# supply_test_2v0.net
KiCad netlist of a schematic drawn in EAGLE
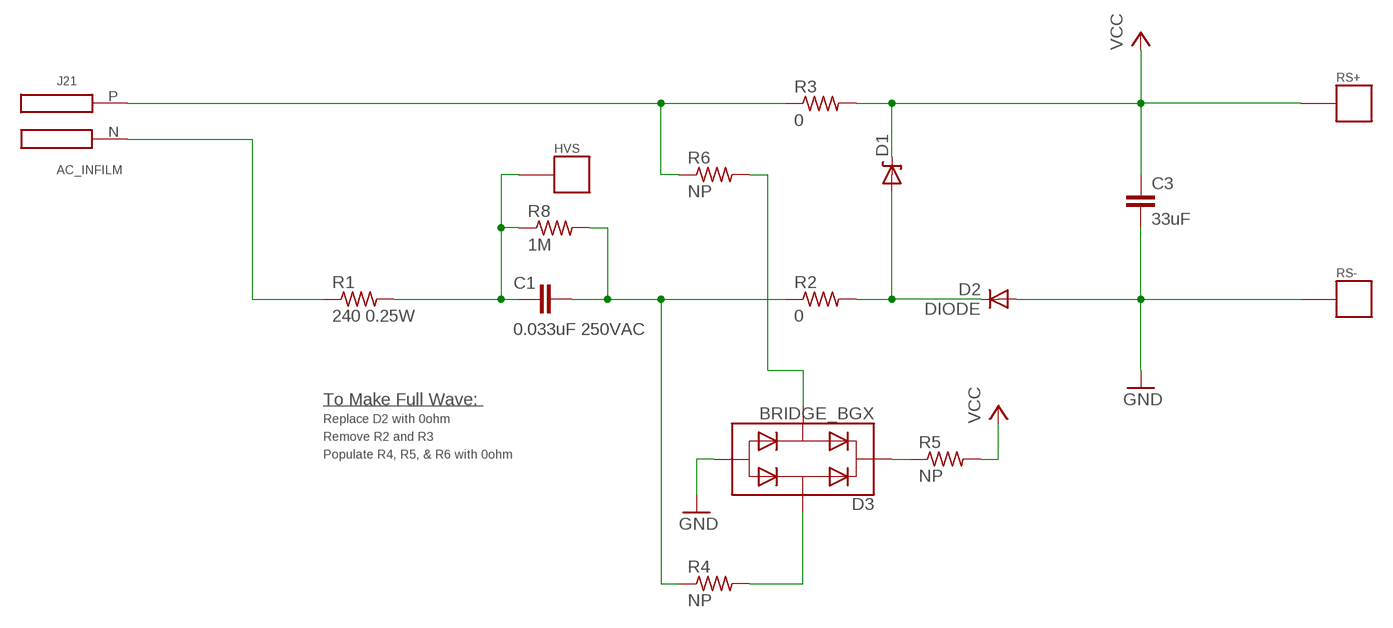
[diagram p0: schematic, sheet 1]
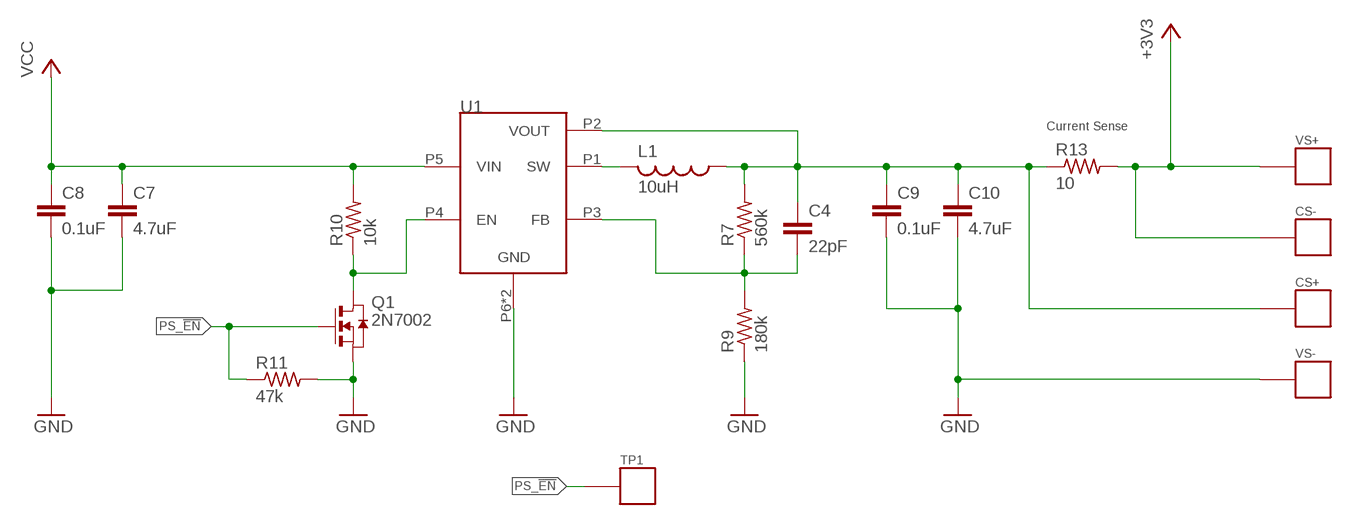
[diagram p1: schematic, sheet 2]
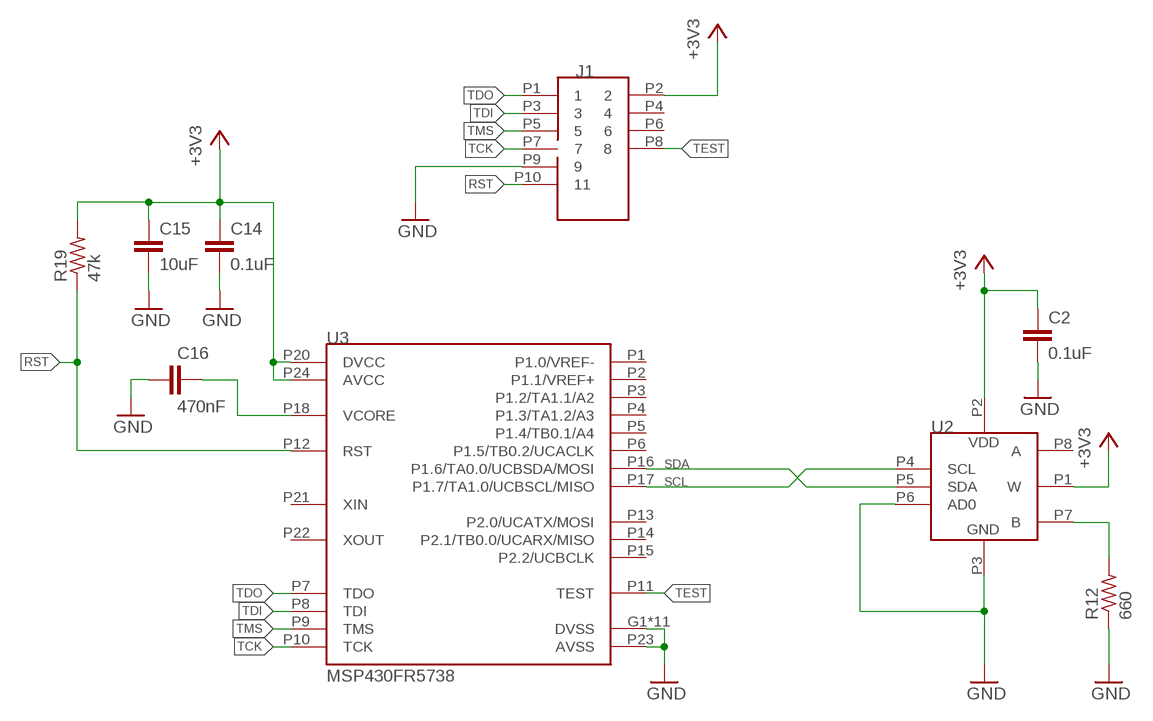
[diagram p2: schematic, sheet 3]

(export (version "E")
  (design (tool "Eeschema 10.0.6"))
  (components
    (comp (ref "C1")
      (value "0.033uF 250VAC")
      (footprint "eagle-import:C2220K")
      (libsource (lib "eagle-import") (part "C-EUC2220K"))
    )
    (comp (ref "C3")
      (value "33uF")
      (footprint "eagle-import:C0603")
      (libsource (lib "eagle-import") (part "C-EUC0603"))
    )
    (comp (ref "D1")
      (value "ZENERBZT52")
      (footprint "eagle-import:BZT52")
      (fields (field (name "DIGIKEY") "BZT52C10T-7DICT-ND "))
      (libsource (lib "eagle-import") (part "ZENERBZT52"))
    )
    (comp (ref "D2")
      (value "DIODE")
      (footprint "eagle-import:BAS521")
      (libsource (lib "eagle-import") (part "DIODE"))
    )
    (comp (ref "D3")
      (value "BRIDGE_BGX")
      (footprint "eagle-import:TO-253-4")
      (libsource (lib "eagle-import") (part "BRIDGE_BGX"))
    )
    (comp (ref "HVS")
      (value "TP_STD")
      (footprint "eagle-import:TP")
      (libsource (lib "eagle-import") (part "TP_STD"))
    )
    (comp (ref "J21")
      (value "AC_INFILM")
      (footprint "eagle-import:AC3_FILM")
      (libsource (lib "eagle-import") (part "AC_INFILM"))
    )
    (comp (ref "R1")
      (value "240 0.25W")
      (footprint "eagle-import:R0603")
      (libsource (lib "eagle-import") (part "R-US_R0603"))
    )
    (comp (ref "R2")
      (value "0")
      (footprint "eagle-import:R0603")
      (libsource (lib "eagle-import") (part "R-US_R0603"))
    )
    (comp (ref "R3")
      (value "0")
      (footprint "eagle-import:R0603")
      (libsource (lib "eagle-import") (part "R-US_R0603"))
    )
    (comp (ref "R4")
      (value "NP")
      (footprint "eagle-import:R0603")
      (libsource (lib "eagle-import") (part "R-US_R0603"))
    )
    (comp (ref "R5")
      (value "NP")
      (footprint "eagle-import:R0603")
      (libsource (lib "eagle-import") (part "R-US_R0603"))
    )
    (comp (ref "R6")
      (value "NP")
      (footprint "eagle-import:R0603")
      (libsource (lib "eagle-import") (part "R-US_R0603"))
    )
    (comp (ref "R8")
      (value "1M")
      (footprint "eagle-import:R0603")
      (libsource (lib "eagle-import") (part "R-US_R0603"))
    )
    (comp (ref "RS+")
      (value "TP_STD")
      (footprint "eagle-import:TP")
      (libsource (lib "eagle-import") (part "TP_STD"))
    )
    (comp (ref "RS-")
      (value "TP_STD")
      (footprint "eagle-import:TP")
      (libsource (lib "eagle-import") (part "TP_STD"))
    )
    (comp (ref "C4")
      (value "22pF")
      (footprint "eagle-import:C0603")
      (libsource (lib "eagle-import") (part "C-EUC0603"))
    )
    (comp (ref "C7")
      (value "4.7uF")
      (footprint "eagle-import:C0402")
      (libsource (lib "eagle-import") (part "C-EUC0402"))
    )
    (comp (ref "C8")
      (value "0.1uF")
      (footprint "eagle-import:C0402")
      (libsource (lib "eagle-import") (part "C-EUC0402"))
    )
    (comp (ref "C9")
      (value "0.1uF")
      (footprint "eagle-import:C0402")
      (libsource (lib "eagle-import") (part "C-EUC0402"))
    )
    (comp (ref "C10")
      (value "4.7uF")
      (footprint "eagle-import:C0603")
      (libsource (lib "eagle-import") (part "C-EUC0603"))
    )
    (comp (ref "CS+")
      (value "TP_STD")
      (footprint "eagle-import:TP")
      (libsource (lib "eagle-import") (part "TP_STD"))
    )
    (comp (ref "CS-")
      (value "TP_STD")
      (footprint "eagle-import:TP")
      (libsource (lib "eagle-import") (part "TP_STD"))
    )
    (comp (ref "L1")
      (value "10uH")
      (footprint "eagle-import:L0805")
      (libsource (lib "eagle-import") (part "L-USL0805"))
    )
    (comp (ref "Q1")
      (value "2N7002")
      (footprint "eagle-import:SC-70-3")
      (libsource (lib "eagle-import") (part "2N7002"))
    )
    (comp (ref "R7")
      (value "560k")
      (footprint "eagle-import:R0603")
      (libsource (lib "eagle-import") (part "R-US_R0603"))
    )
    (comp (ref "R9")
      (value "180k")
      (footprint "eagle-import:R0603")
      (libsource (lib "eagle-import") (part "R-US_R0603"))
    )
    (comp (ref "R10")
      (value "10k")
      (footprint "eagle-import:R0402")
      (libsource (lib "eagle-import") (part "R-US_R0402"))
    )
    (comp (ref "R11")
      (value "47k")
      (footprint "eagle-import:R0603")
      (libsource (lib "eagle-import") (part "R-US_R0603"))
    )
    (comp (ref "R13")
      (value "10")
      (footprint "eagle-import:R0603")
      (libsource (lib "eagle-import") (part "R-US_R0603"))
    )
    (comp (ref "TP1")
      (value "TP_STD")
      (footprint "eagle-import:TP")
      (libsource (lib "eagle-import") (part "TP_STD"))
    )
    (comp (ref "U1")
      (value "TPS62122")
      (footprint "eagle-import:WDFN-6")
      (libsource (lib "eagle-import") (part "TPS62122"))
    )
    (comp (ref "VS+")
      (value "TP_STD")
      (footprint "eagle-import:TP")
      (libsource (lib "eagle-import") (part "TP_STD"))
    )
    (comp (ref "VS-")
      (value "TP_STD")
      (footprint "eagle-import:TP")
      (libsource (lib "eagle-import") (part "TP_STD"))
    )
    (comp (ref "C2")
      (value "0.1uF")
      (footprint "eagle-import:C0603")
      (libsource (lib "eagle-import") (part "C-EUC0603"))
    )
    (comp (ref "C14")
      (value "0.1uF")
      (footprint "eagle-import:C0603")
      (libsource (lib "eagle-import") (part "C-EUC0603"))
    )
    (comp (ref "C15")
      (value "10uF")
      (footprint "eagle-import:C0603")
      (libsource (lib "eagle-import") (part "C-EUC0603"))
    )
    (comp (ref "C16")
      (value "470nF")
      (footprint "eagle-import:C0603")
      (libsource (lib "eagle-import") (part "C-EUC0603"))
    )
    (comp (ref "J1")
      (value "JTAG_14PIN_IDC-NL")
      (footprint "eagle-import:TC2050-IDC-NL-430")
      (fields (field (name "TAG-CONNECT") "TC2050-IDC-NL-430"))
      (libsource (lib "eagle-import") (part "JTAG_14PIN_IDC-NL"))
    )
    (comp (ref "R12")
      (value "660")
      (footprint "eagle-import:R0603")
      (libsource (lib "eagle-import") (part "R-US_R0603"))
    )
    (comp (ref "R19")
      (value "47k")
      (footprint "eagle-import:R0603")
      (libsource (lib "eagle-import") (part "R-US_R0603"))
    )
    (comp (ref "U2")
      (value "AD524")
      (footprint "eagle-import:SOT-23-8")
      (libsource (lib "eagle-import") (part "AD524"))
    )
    (comp (ref "U3")
      (value "MSP430FR5738")
      (footprint "eagle-import:VQFN-24")
      (libsource (lib "eagle-import") (part "MSP430FR5738"))
    )
  )
  (nets
    (net (code "1") (name "+3V3") (class "Default")
      (node (ref "C14") (pin "1") (pinfunction "1_1") (pintype "passive"))
      (node (ref "C15") (pin "1") (pinfunction "1_1") (pintype "passive"))
      (node (ref "C2") (pin "1") (pinfunction "1_1") (pintype "passive"))
      (node (ref "CS-") (pin "P$1") (pinfunction "P$1_P$1") (pintype "bidirectional"))
      (node (ref "J1") (pin "P2") (pinfunction "2_P2") (pintype "bidirectional"))
      (node (ref "R13") (pin "2") (pinfunction "2_2") (pintype "passive"))
      (node (ref "R19") (pin "2") (pinfunction "2_2") (pintype "passive"))
      (node (ref "U2") (pin "P1") (pinfunction "W_P1") (pintype "bidirectional"))
      (node (ref "U2") (pin "P2") (pinfunction "VDD_P2") (pintype "bidirectional"))
      (node (ref "U3") (pin "P20") (pinfunction "DVCC_P20") (pintype "bidirectional"))
      (node (ref "U3") (pin "P24") (pinfunction "AVCC_P24") (pintype "bidirectional"))
      (node (ref "VS+") (pin "P$1") (pinfunction "P$1_P$1") (pintype "bidirectional"))
    )
    (net (code "2") (name "GND") (class "Default")
      (node (ref "C10") (pin "2") (pinfunction "2_2") (pintype "passive"))
      (node (ref "C14") (pin "2") (pinfunction "2_2") (pintype "passive"))
      (node (ref "C15") (pin "2") (pinfunction "2_2") (pintype "passive"))
      (node (ref "C16") (pin "1") (pinfunction "1_1") (pintype "passive"))
      (node (ref "C2") (pin "2") (pinfunction "2_2") (pintype "passive"))
      (node (ref "C3") (pin "2") (pinfunction "2_2") (pintype "passive"))
      (node (ref "C7") (pin "2") (pinfunction "2_2") (pintype "passive"))
      (node (ref "C8") (pin "2") (pinfunction "2_2") (pintype "passive"))
      (node (ref "C9") (pin "2") (pinfunction "2_2") (pintype "passive"))
      (node (ref "D2") (pin "A") (pinfunction "A_A") (pintype "passive"))
      (node (ref "D3") (pin "P3") (pinfunction "P3_P3") (pintype "passive"))
      (node (ref "J1") (pin "P9") (pinfunction "9_P9") (pintype "bidirectional"))
      (node (ref "Q1") (pin "P2") (pinfunction "S_P2") (pintype "passive"))
      (node (ref "R11") (pin "2") (pinfunction "2_2") (pintype "passive"))
      (node (ref "R12") (pin "1") (pinfunction "1_1") (pintype "passive"))
      (node (ref "R9") (pin "1") (pinfunction "1_1") (pintype "passive"))
      (node (ref "RS-") (pin "P$1") (pinfunction "P$1_P$1") (pintype "bidirectional"))
      (node (ref "U1") (pin "P6") (pinfunction "GND_P6") (pintype "bidirectional"))
      (node (ref "U1") (pin "PAD") (pinfunction "GND_PAD") (pintype "bidirectional"))
      (node (ref "U2") (pin "P3") (pinfunction "GND_P3") (pintype "bidirectional"))
      (node (ref "U2") (pin "P6") (pinfunction "AD0_P6") (pintype "bidirectional"))
      (node (ref "U3") (pin "G1") (pinfunction "DVSS_G1") (pintype "bidirectional"))
      (node (ref "U3") (pin "G2") (pinfunction "DVSS_G2") (pintype "bidirectional"))
      (node (ref "U3") (pin "G3") (pinfunction "DVSS_G3") (pintype "bidirectional"))
      (node (ref "U3") (pin "G4") (pinfunction "DVSS_G4") (pintype "bidirectional"))
      (node (ref "U3") (pin "G5") (pinfunction "DVSS_G5") (pintype "bidirectional"))
      (node (ref "U3") (pin "G6") (pinfunction "DVSS_G6") (pintype "bidirectional"))
      (node (ref "U3") (pin "G7") (pinfunction "DVSS_G7") (pintype "bidirectional"))
      (node (ref "U3") (pin "G8") (pinfunction "DVSS_G8") (pintype "bidirectional"))
      (node (ref "U3") (pin "G9") (pinfunction "DVSS_G9") (pintype "bidirectional"))
      (node (ref "U3") (pin "P19") (pinfunction "DVSS_P19") (pintype "bidirectional"))
      (node (ref "U3") (pin "P23") (pinfunction "AVSS_P23") (pintype "bidirectional"))
      (node (ref "U3") (pin "PAD") (pinfunction "DVSS_PAD") (pintype "bidirectional"))
      (node (ref "VS-") (pin "P$1") (pinfunction "P$1_P$1") (pintype "bidirectional"))
    )
    (net (code "3") (name "Net-(C1-Pad1)") (class "Default")
      (node (ref "C1") (pin "1") (pinfunction "1_1") (pintype "passive"))
      (node (ref "R2") (pin "1") (pinfunction "1_1") (pintype "passive"))
      (node (ref "R4") (pin "1") (pinfunction "1_1") (pintype "passive"))
      (node (ref "R8") (pin "2") (pinfunction "2_2") (pintype "passive"))
    )
    (net (code "4") (name "Net-(C1-Pad2)") (class "Default")
      (node (ref "C1") (pin "2") (pinfunction "2_2") (pintype "passive"))
      (node (ref "HVS") (pin "P$1") (pinfunction "P$1_P$1") (pintype "bidirectional"))
      (node (ref "R1") (pin "2") (pinfunction "2_2") (pintype "passive"))
      (node (ref "R8") (pin "1") (pinfunction "1_1") (pintype "passive"))
    )
    (net (code "5") (name "Net-(D1-PadA)") (class "Default")
      (node (ref "D1") (pin "A") (pinfunction "A_A") (pintype "passive"))
      (node (ref "D2") (pin "C") (pinfunction "C_C") (pintype "passive"))
      (node (ref "R2") (pin "2") (pinfunction "2_2") (pintype "passive"))
    )
    (net (code "6") (name "Net-(D3-PadP1)") (class "Default")
      (node (ref "D3") (pin "P1") (pinfunction "P1_P1") (pintype "passive"))
      (node (ref "R5") (pin "1") (pinfunction "1_1") (pintype "passive"))
    )
    (net (code "7") (name "Net-(D3-PadP2)") (class "Default")
      (node (ref "D3") (pin "P2") (pinfunction "P2_P2") (pintype "passive"))
      (node (ref "R6") (pin "2") (pinfunction "2_2") (pintype "passive"))
    )
    (net (code "8") (name "Net-(D3-PadP4)") (class "Default")
      (node (ref "D3") (pin "P4") (pinfunction "P4_P4") (pintype "passive"))
      (node (ref "R4") (pin "2") (pinfunction "2_2") (pintype "passive"))
    )
    (net (code "9") (name "Net-(J21-PadN)") (class "Default")
      (node (ref "J21") (pin "N") (pinfunction "N_N") (pintype "bidirectional"))
      (node (ref "R1") (pin "1") (pinfunction "1_1") (pintype "passive"))
    )
    (net (code "10") (name "Net-(J21-PadP)") (class "Default")
      (node (ref "J21") (pin "P") (pinfunction "P_P") (pintype "bidirectional"))
      (node (ref "R3") (pin "1") (pinfunction "1_1") (pintype "passive"))
      (node (ref "R6") (pin "1") (pinfunction "1_1") (pintype "passive"))
    )
    (net (code "11") (name "Net-(Q1-D)") (class "Default")
      (node (ref "Q1") (pin "P3") (pinfunction "D_P3") (pintype "passive"))
      (node (ref "R10") (pin "1") (pinfunction "1_1") (pintype "passive"))
      (node (ref "U1") (pin "P4") (pinfunction "EN_P4") (pintype "bidirectional"))
    )
    (net (code "12") (name "Net-(U1-FB)") (class "Default")
      (node (ref "C4") (pin "2") (pinfunction "2_2") (pintype "passive"))
      (node (ref "R7") (pin "1") (pinfunction "1_1") (pintype "passive"))
      (node (ref "R9") (pin "2") (pinfunction "2_2") (pintype "passive"))
      (node (ref "U1") (pin "P3") (pinfunction "FB_P3") (pintype "bidirectional"))
    )
    (net (code "13") (name "Net-(U1-SW)") (class "Default")
      (node (ref "L1") (pin "2") (pinfunction "2_2") (pintype "passive"))
      (node (ref "U1") (pin "P1") (pinfunction "SW_P1") (pintype "bidirectional"))
    )
    (net (code "14") (name "Net-(U1-VOUT)") (class "Default")
      (node (ref "C10") (pin "1") (pinfunction "1_1") (pintype "passive"))
      (node (ref "C4") (pin "1") (pinfunction "1_1") (pintype "passive"))
      (node (ref "C9") (pin "1") (pinfunction "1_1") (pintype "passive"))
      (node (ref "CS+") (pin "P$1") (pinfunction "P$1_P$1") (pintype "bidirectional"))
      (node (ref "L1") (pin "1") (pinfunction "1_1") (pintype "passive"))
      (node (ref "R13") (pin "1") (pinfunction "1_1") (pintype "passive"))
      (node (ref "R7") (pin "2") (pinfunction "2_2") (pintype "passive"))
      (node (ref "U1") (pin "P2") (pinfunction "VOUT_P2") (pintype "bidirectional"))
    )
    (net (code "15") (name "Net-(U2-B)") (class "Default")
      (node (ref "R12") (pin "2") (pinfunction "2_2") (pintype "passive"))
      (node (ref "U2") (pin "P7") (pinfunction "B_P7") (pintype "bidirectional"))
    )
    (net (code "16") (name "Net-(U3-VCORE)") (class "Default")
      (node (ref "C16") (pin "2") (pinfunction "2_2") (pintype "passive"))
      (node (ref "U3") (pin "P18") (pinfunction "VCORE_P18") (pintype "bidirectional"))
    )
    (net (code "17") (name "PS_~{EN}") (class "Default")
      (node (ref "Q1") (pin "P1") (pinfunction "G_P1") (pintype "passive"))
      (node (ref "R11") (pin "1") (pinfunction "1_1") (pintype "passive"))
      (node (ref "TP1") (pin "P$1") (pinfunction "P$1_P$1") (pintype "bidirectional"))
    )
    (net (code "18") (name "RST") (class "Default")
      (node (ref "J1") (pin "P10") (pinfunction "11_P10") (pintype "bidirectional"))
      (node (ref "R19") (pin "1") (pinfunction "1_1") (pintype "passive"))
      (node (ref "U3") (pin "P12") (pinfunction "RST_P12") (pintype "bidirectional"))
    )
    (net (code "19") (name "SCL") (class "Default")
      (node (ref "U2") (pin "P4") (pinfunction "SCL_P4") (pintype "bidirectional"))
      (node (ref "U3") (pin "P17") (pinfunction "P1.7/TA1.0/UCBSCL/MISO_P17") (pintype "bidirectional"))
    )
    (net (code "20") (name "SDA") (class "Default")
      (node (ref "U2") (pin "P5") (pinfunction "SDA_P5") (pintype "bidirectional"))
      (node (ref "U3") (pin "P16") (pinfunction "P1.6/TA0.0/UCBSDA/MOSI_P16") (pintype "bidirectional"))
    )
    (net (code "21") (name "TCK") (class "Default")
      (node (ref "J1") (pin "P7") (pinfunction "7_P7") (pintype "bidirectional"))
      (node (ref "U3") (pin "P10") (pinfunction "TCK_P10") (pintype "bidirectional"))
    )
    (net (code "22") (name "TDI") (class "Default")
      (node (ref "J1") (pin "P3") (pinfunction "3_P3") (pintype "bidirectional"))
      (node (ref "U3") (pin "P8") (pinfunction "TDI_P8") (pintype "bidirectional"))
    )
    (net (code "23") (name "TDO") (class "Default")
      (node (ref "J1") (pin "P1") (pinfunction "1_P1") (pintype "bidirectional"))
      (node (ref "U3") (pin "P7") (pinfunction "TDO_P7") (pintype "bidirectional"))
    )
    (net (code "24") (name "TEST") (class "Default")
      (node (ref "J1") (pin "P8") (pinfunction "8_P8") (pintype "bidirectional"))
      (node (ref "U3") (pin "P11") (pinfunction "TEST_P11") (pintype "bidirectional"))
    )
    (net (code "25") (name "TMS") (class "Default")
      (node (ref "J1") (pin "P5") (pinfunction "5_P5") (pintype "bidirectional"))
      (node (ref "U3") (pin "P9") (pinfunction "TMS_P9") (pintype "bidirectional"))
    )
    (net (code "26") (name "VCC") (class "Default")
      (node (ref "C3") (pin "1") (pinfunction "1_1") (pintype "passive"))
      (node (ref "C7") (pin "1") (pinfunction "1_1") (pintype "passive"))
      (node (ref "C8") (pin "1") (pinfunction "1_1") (pintype "passive"))
      (node (ref "D1") (pin "C") (pinfunction "C_C") (pintype "passive"))
      (node (ref "R10") (pin "2") (pinfunction "2_2") (pintype "passive"))
      (node (ref "R3") (pin "2") (pinfunction "2_2") (pintype "passive"))
      (node (ref "R5") (pin "2") (pinfunction "2_2") (pintype "passive"))
      (node (ref "RS+") (pin "P$1") (pinfunction "P$1_P$1") (pintype "bidirectional"))
      (node (ref "U1") (pin "P5") (pinfunction "VIN_P5") (pintype "bidirectional"))
    )
    (net (code "27") (name "unconnected-(J1-4-PadP4)") (class "Default")
      (node (ref "J1") (pin "P4") (pinfunction "4_P4") (pintype "bidirectional"))
    )
    (net (code "28") (name "unconnected-(J1-6-PadP6)") (class "Default")
      (node (ref "J1") (pin "P6") (pinfunction "6_P6") (pintype "bidirectional"))
    )
    (net (code "29") (name "unconnected-(U2-A-PadP8)") (class "Default")
      (node (ref "U2") (pin "P8") (pinfunction "A_P8") (pintype "bidirectional"))
    )
    (net (code "30") (name "unconnected-(U3-P1.0{slash}VREF--PadP1)") (class "Default")
      (node (ref "U3") (pin "P1") (pinfunction "P1.0/VREF-_P1") (pintype "bidirectional"))
    )
    (net (code "31") (name "unconnected-(U3-P1.1{slash}VREF+-PadP2)") (class "Default")
      (node (ref "U3") (pin "P2") (pinfunction "P1.1/VREF+_P2") (pintype "bidirectional"))
    )
    (net (code "32") (name "unconnected-(U3-P1.2{slash}TA1.1{slash}A2-PadP3)") (class "Default")
      (node (ref "U3") (pin "P3") (pinfunction "P1.2/TA1.1/A2_P3") (pintype "bidirectional"))
    )
    (net (code "33") (name "unconnected-(U3-P1.3{slash}TA1.2{slash}A3-PadP4)") (class "Default")
      (node (ref "U3") (pin "P4") (pinfunction "P1.3/TA1.2/A3_P4") (pintype "bidirectional"))
    )
    (net (code "34") (name "unconnected-(U3-P1.4{slash}TB0.1{slash}A4-PadP5)") (class "Default")
      (node (ref "U3") (pin "P5") (pinfunction "P1.4/TB0.1/A4_P5") (pintype "bidirectional"))
    )
    (net (code "35") (name "unconnected-(U3-P1.5{slash}TB0.2{slash}UCACLK-PadP6)") (class "Default")
      (node (ref "U3") (pin "P6") (pinfunction "P1.5/TB0.2/UCACLK_P6") (pintype "bidirectional"))
    )
    (net (code "36") (name "unconnected-(U3-P2.0{slash}UCATX{slash}MOSI-PadP13)") (class "Default")
      (node (ref "U3") (pin "P13") (pinfunction "P2.0/UCATX/MOSI_P13") (pintype "bidirectional"))
    )
    (net (code "37") (name "unconnected-(U3-P2.1{slash}TB0.0{slash}UCARX{slash}MISO-PadP14)") (class "Default")
      (node (ref "U3") (pin "P14") (pinfunction "P2.1/TB0.0/UCARX/MISO_P14") (pintype "bidirectional"))
    )
    (net (code "38") (name "unconnected-(U3-P2.2{slash}UCBCLK-PadP15)") (class "Default")
      (node (ref "U3") (pin "P15") (pinfunction "P2.2/UCBCLK_P15") (pintype "bidirectional"))
    )
    (net (code "39") (name "unconnected-(U3-XIN-PadP21)") (class "Default")
      (node (ref "U3") (pin "P21") (pinfunction "XIN_P21") (pintype "bidirectional"))
    )
    (net (code "40") (name "unconnected-(U3-XOUT-PadP22)") (class "Default")
      (node (ref "U3") (pin "P22") (pinfunction "XOUT_P22") (pintype "bidirectional"))
    )
  )
)
